# Sheet7.net
KiCad netlist of a schematic drawn in Altium Designer
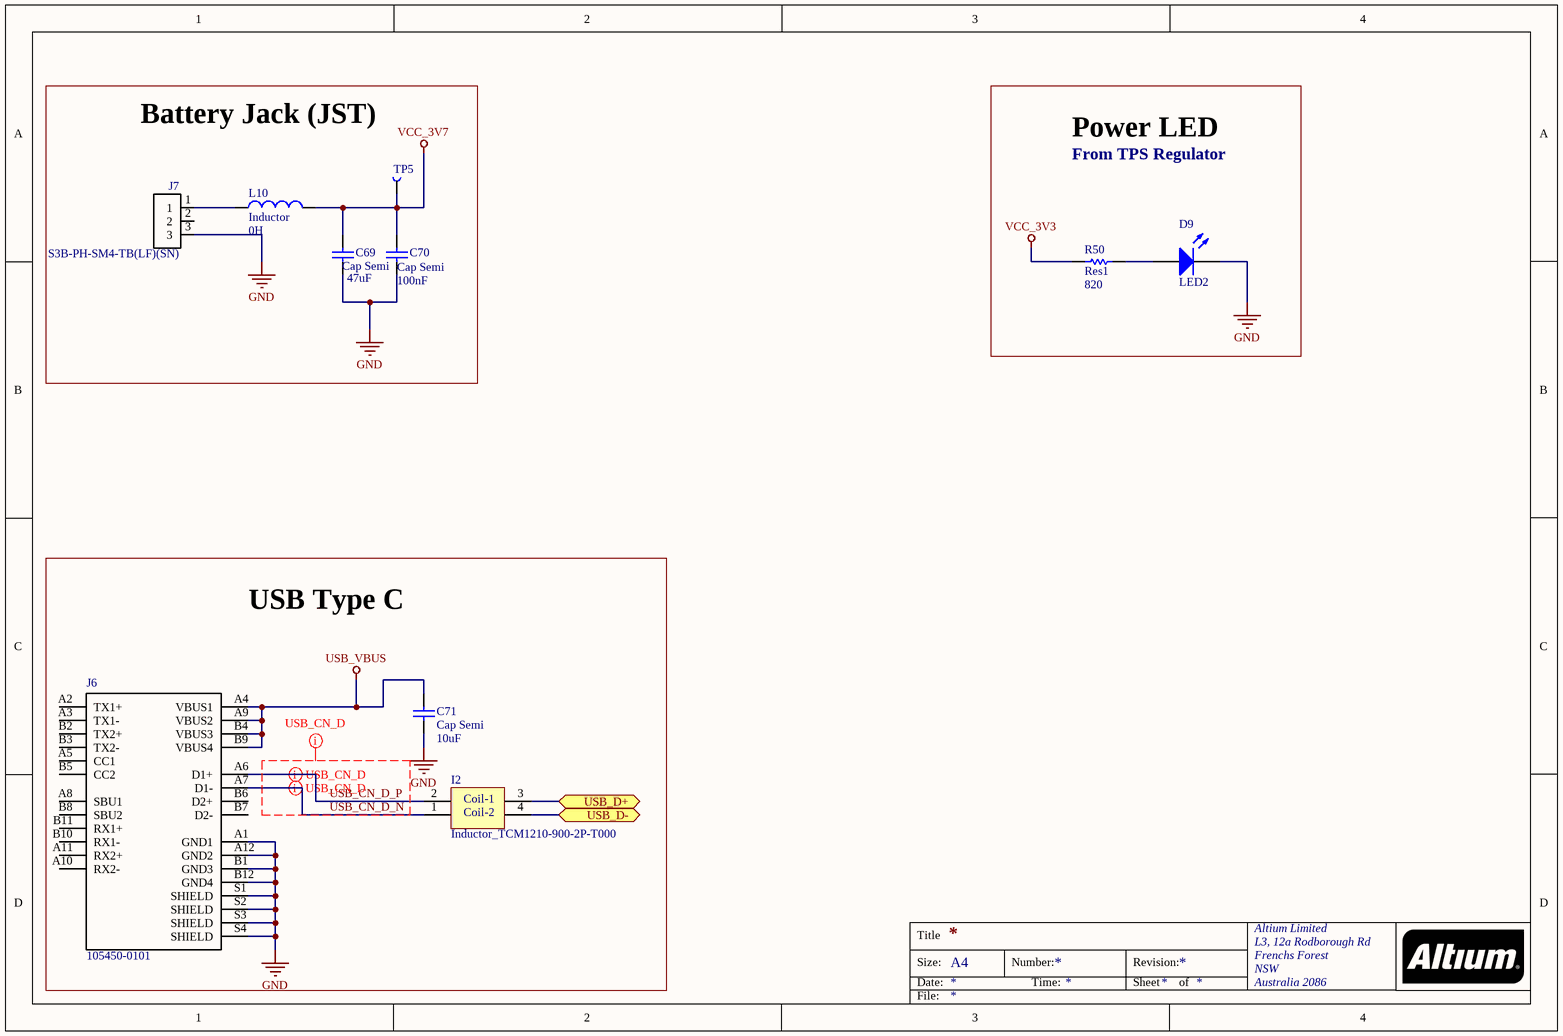
[diagram p0: Sheet7.SchDoc]

(export (version "E")
  (design (tool "Eeschema 10.0.6"))
  (components
    (comp (ref "C69")
      (value "Cap Semi")
      (footprint "CAP 1206/3216")
      (description "47µF ±20% 10V Ceramic Capacitor X5R 1206 (3216 Metric)")
      (fields
        (field (name "PART NUMBER") "LMK316BJ476ML-T")
        (field (name "ALTIUM_VALUE") "47uF")
        (field (name "PUBLISHER") "Altium Limited")
      )
      (libsource (lib "Miscellaneous Devices") (part "Cap Semi"))
    )
    (comp (ref "C70")
      (value "Cap Semi")
      (footprint "CAP 0402/1005")
      (description "0.1µF -20%, +80% 16V Ceramic Capacitor Y5V (F) 0402 (1005 Metric)")
      (fields (field (name "PART NUMBER") "VJ0402V104ZXJCW1BC") (field (name "ALTIUM_VALUE") "100nF"))
      (libsource (lib "Miscellaneous Devices") (part "Cap Semi"))
    )
    (comp (ref "C71")
      (value "Cap Semi")
      (footprint "CAP 0603/1608")
      (description "10µF ±20% 10V Ceramic Capacitor X5R 0603 (1608 Metric)")
      (fields
        (field (name "PART NUMBER") "GRM188R61A106ME69D")
        (field (name "ALTIUM_VALUE") "10uF")
        (field (name "PUBLISHER") "Altium Limited")
      )
      (libsource (lib "Miscellaneous Devices") (part "Cap Semi"))
    )
    (comp (ref "D9")
      (value "LED2")
      (footprint "LED_0603 - 3D")
      (description "Green 570nm LED Indication - Discrete 1.7V 0603 (1608 Metric)")
      (fields (field (name "PART NUMBER") "LG L29K-F2J1-24-Z") (field (name "PUBLISHER") "Altium Limited"))
      (libsource (lib "Miscellaneous Devices") (part "LED2"))
    )
    (comp (ref "I2")
      (value "Inductor_TCM1210-900-2P-T000")
      (footprint "Inductor_TCM1210-900-2P-T000")
      (description "Common Mode Chokes / Filters")
      (fields (field (name "PART NUMBER") "TCM1210-900-2P-T000"))
      (libsource (lib "Inductor_TCM1210-900-2P-T000") (part "Inductor_TCM1210-900-2P-T000"))
    )
    (comp (ref "J6")
      (value "105450-0101")
      (footprint "*MOLEX_105450-0101")
      (fields (field (name "PART NUMBER") "1054500101") (field (name "MF") "Molex"))
      (libsource (lib "USB Type C Port SMD") (part "105450-0101"))
    )
    (comp (ref "J7")
      (value "S3B-PH-SM4-TB(LF)(SN)")
      (footprint "*JST_S3B-PH-SM4-TB(LF)(SN)")
      (description "Connector Header Surface Mount, Right Angle 3 position 0.079\" (2.00mm)")
      (fields (field (name "MF") "JST Sales"))
      (libsource (lib "JST S3B-PH-SM4-TB_LF__SN_") (part "S3B-PH-SM4-TB(LF)(SN)"))
    )
    (comp (ref "L10")
      (value "Inductor")
      (footprint "INDC1608L")
      (description "220 Ohms @ 100MHz 1 Power Line Ferrite Bead 0603 (1608 Metric) 2.2A 50 mOhm")
      (fields
        (field (name "ALTIUM_VALUE") "0H")
        (field (name "PART NUMBER") "MPZ1608S221ATA00")
        (field (name "PUBLISHER") "Altium Limited")
      )
      (libsource (lib "Miscellaneous Devices") (part "Inductor"))
    )
    (comp (ref "R50")
      (value "Res1")
      (footprint "RES 0402/1005")
      (description "820 Ohms ±5% 0.1W, 1/10W Chip Resistor 0402 (1005 Metric) Automotive AEC-Q200 Thick Film")
      (fields (field (name "PART NUMBER") "RK73B1ETTP821J") (field (name "ALTIUM_VALUE") "820"))
      (libsource (lib "Miscellaneous Devices") (part "Res1"))
    )
    (comp (ref "TP5")
      (value "TestPoint")
      (footprint "TestPoint")
      (libsource (lib "TestPoint") (part "TestPoint"))
    )
  )
  (nets
    (net (code "1") (name "/USB_CN_D_N") (class "Default")
      (node (ref "I2") (pin "1") (pintype "passive"))
      (node (ref "J6") (pin "A7") (pinfunction "D1-_A7") (pintype "passive"))
    )
    (net (code "2") (name "/USB_CN_D_P") (class "Default")
      (node (ref "I2") (pin "2") (pintype "passive"))
      (node (ref "J6") (pin "A6") (pinfunction "D1+_A6") (pintype "passive"))
    )
    (net (code "3") (name "/USB_D+") (class "Default") (node (ref "I2") (pin "3") (pintype "passive")))
    (net (code "4") (name "/USB_D-") (class "Default") (node (ref "I2") (pin "4") (pintype "passive")))
    (net (code "5") (name "GND") (class "Default")
      (node (ref "C69") (pin "1") (pinfunction "1_1") (pintype "passive"))
      (node (ref "C70") (pin "1") (pinfunction "1_1") (pintype "passive"))
      (node (ref "C71") (pin "1") (pinfunction "1_1") (pintype "passive"))
      (node (ref "D9") (pin "2") (pinfunction "K_2") (pintype "passive"))
      (node (ref "J6") (pin "A1") (pinfunction "GND1_A1") (pintype "passive"))
      (node (ref "J6") (pin "A12") (pinfunction "GND2_A12") (pintype "passive"))
      (node (ref "J6") (pin "B1") (pinfunction "GND3_B1") (pintype "passive"))
      (node (ref "J6") (pin "B12") (pinfunction "GND4_B12") (pintype "passive"))
      (node (ref "J6") (pin "S1") (pinfunction "SHIELD_S1") (pintype "passive"))
      (node (ref "J6") (pin "S2") (pinfunction "SHIELD_S2") (pintype "passive"))
      (node (ref "J6") (pin "S3") (pinfunction "SHIELD_S3") (pintype "passive"))
      (node (ref "J6") (pin "S4") (pinfunction "SHIELD_S4") (pintype "passive"))
      (node (ref "J7") (pin "3") (pinfunction "3_3") (pintype "passive"))
    )
    (net (code "6") (name "Net-(D9-A)") (class "Default")
      (node (ref "D9") (pin "1") (pinfunction "A_1") (pintype "passive"))
      (node (ref "R50") (pin "1") (pinfunction "1_1") (pintype "passive"))
    )
    (net (code "7") (name "Net-(J7-Pad1)") (class "Default")
      (node (ref "J7") (pin "1") (pinfunction "1_1") (pintype "passive"))
      (node (ref "L10") (pin "1") (pinfunction "1_1") (pintype "passive"))
    )
    (net (code "8") (name "USB_VBUS") (class "Default")
      (node (ref "C71") (pin "2") (pinfunction "2_2") (pintype "passive"))
      (node (ref "J6") (pin "A4") (pinfunction "VBUS1_A4") (pintype "passive"))
      (node (ref "J6") (pin "A9") (pinfunction "VBUS2_A9") (pintype "passive"))
      (node (ref "J6") (pin "B4") (pinfunction "VBUS3_B4") (pintype "passive"))
      (node (ref "J6") (pin "B9") (pinfunction "VBUS4_B9") (pintype "passive"))
    )
    (net (code "9") (name "VCC_3V3") (class "Default")
      (node (ref "R50") (pin "2") (pinfunction "2_2") (pintype "passive"))
    )
    (net (code "10") (name "VCC_3V7") (class "Default")
      (node (ref "C69") (pin "2") (pinfunction "2_2") (pintype "passive"))
      (node (ref "C70") (pin "2") (pinfunction "2_2") (pintype "passive"))
      (node (ref "L10") (pin "2") (pinfunction "2_2") (pintype "passive"))
      (node (ref "TP5") (pin "1") (pinfunction "TP_1") (pintype "passive"))
    )
    (net (code "11") (name "unconnected-(J6-CC1-PadA5)") (class "Default")
      (node (ref "J6") (pin "A5") (pinfunction "CC1_A5") (pintype "passive"))
    )
    (net (code "12") (name "unconnected-(J6-CC2-PadB5)") (class "Default")
      (node (ref "J6") (pin "B5") (pinfunction "CC2_B5") (pintype "passive"))
    )
    (net (code "13") (name "unconnected-(J6-D2+-PadB6)") (class "Default")
      (node (ref "J6") (pin "B6") (pinfunction "D2+_B6") (pintype "passive"))
    )
    (net (code "14") (name "unconnected-(J6-D2--PadB7)") (class "Default")
      (node (ref "J6") (pin "B7") (pinfunction "D2-_B7") (pintype "passive"))
    )
    (net (code "15") (name "unconnected-(J6-RX1+-PadB11)") (class "Default")
      (node (ref "J6") (pin "B11") (pinfunction "RX1+_B11") (pintype "passive"))
    )
    (net (code "16") (name "unconnected-(J6-RX1--PadB10)") (class "Default")
      (node (ref "J6") (pin "B10") (pinfunction "RX1-_B10") (pintype "passive"))
    )
    (net (code "17") (name "unconnected-(J6-RX2+-PadA11)") (class "Default")
      (node (ref "J6") (pin "A11") (pinfunction "RX2+_A11") (pintype "passive"))
    )
    (net (code "18") (name "unconnected-(J6-RX2--PadA10)") (class "Default")
      (node (ref "J6") (pin "A10") (pinfunction "RX2-_A10") (pintype "passive"))
    )
    (net (code "19") (name "unconnected-(J6-SBU1-PadA8)") (class "Default")
      (node (ref "J6") (pin "A8") (pinfunction "SBU1_A8") (pintype "passive"))
    )
    (net (code "20") (name "unconnected-(J6-SBU2-PadB8)") (class "Default")
      (node (ref "J6") (pin "B8") (pinfunction "SBU2_B8") (pintype "passive"))
    )
    (net (code "21") (name "unconnected-(J6-TX1+-PadA2)") (class "Default")
      (node (ref "J6") (pin "A2") (pinfunction "TX1+_A2") (pintype "passive"))
    )
    (net (code "22") (name "unconnected-(J6-TX1--PadA3)") (class "Default")
      (node (ref "J6") (pin "A3") (pinfunction "TX1-_A3") (pintype "passive"))
    )
    (net (code "23") (name "unconnected-(J6-TX2+-PadB2)") (class "Default")
      (node (ref "J6") (pin "B2") (pinfunction "TX2+_B2") (pintype "passive"))
    )
    (net (code "24") (name "unconnected-(J6-TX2--PadB3)") (class "Default")
      (node (ref "J6") (pin "B3") (pinfunction "TX2-_B3") (pintype "passive"))
    )
    (net (code "25") (name "unconnected-(J7-Pad2)") (class "Default")
      (node (ref "J7") (pin "2") (pinfunction "2_2") (pintype "passive"))
    )
  )
)
